# 2_isoSPI.net
KiCad netlist of a schematic drawn in Altium Designer
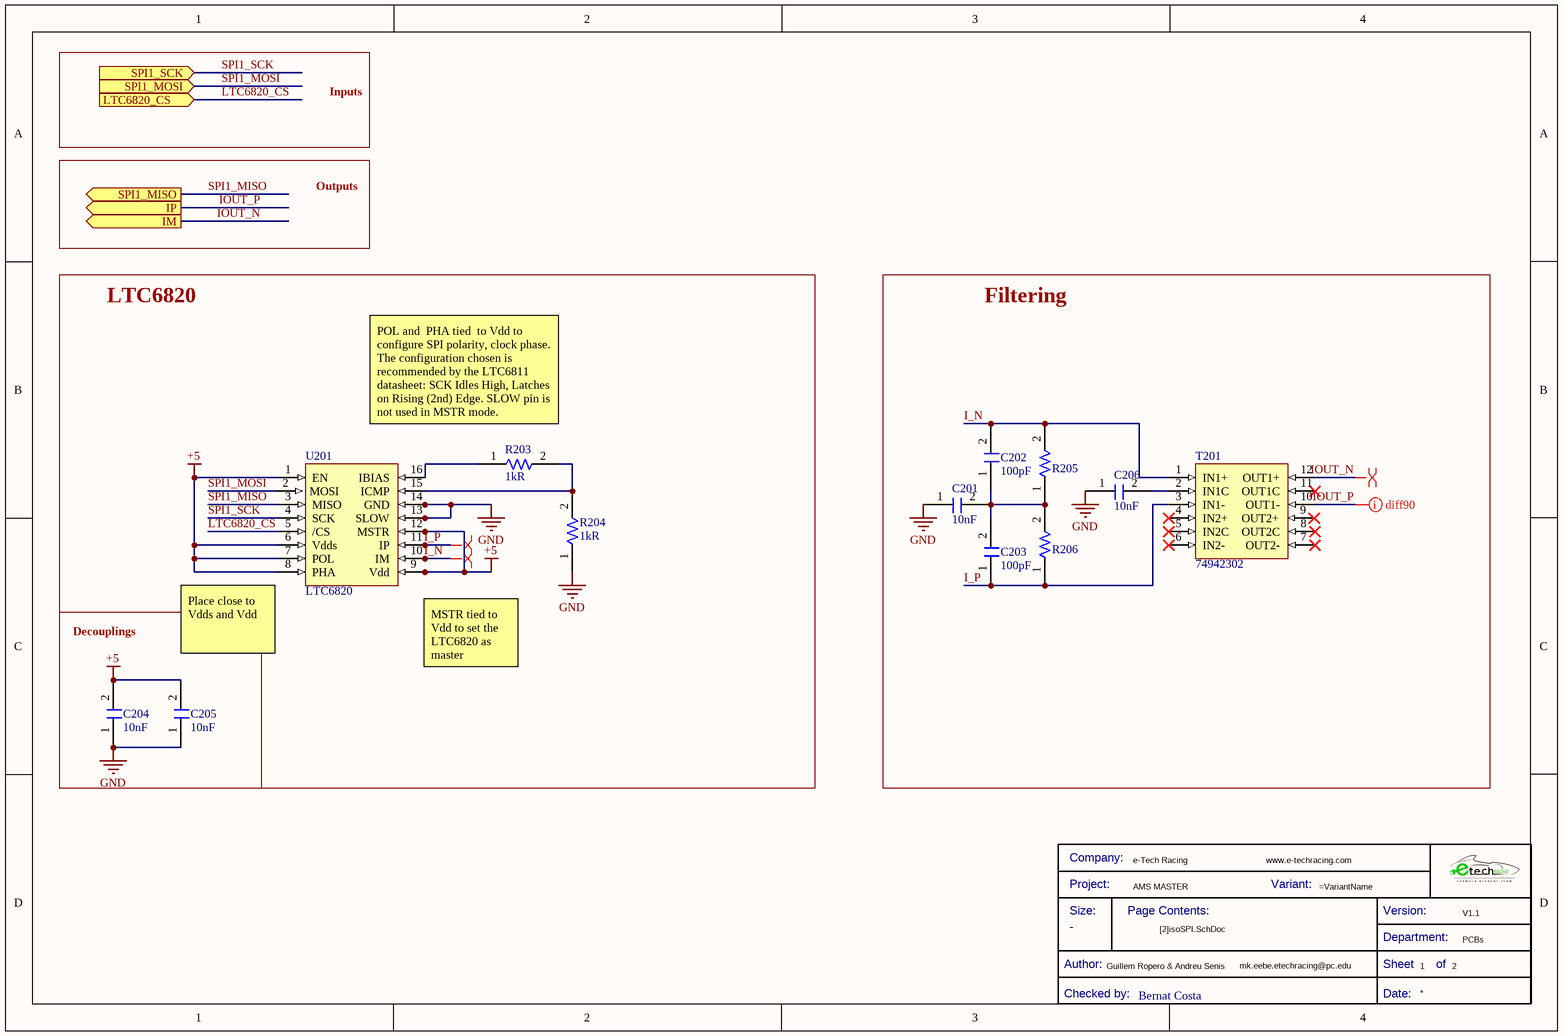
[diagram p0: [2]isoSPI.SchDoc]

(export (version "E")
  (design (tool "Eeschema 10.0.6"))
  (components
    (comp (ref "C201")
      (value "885012008055")
      (footprint "C1206FNPC-RW")
      (description "Cap Cer 10000PF 50V C0G/NP0 1206")
      (fields
        (field (name "MANUFACTURER") "Wurth Electronics")
        (field (name "TOLERANCE") "5%")
        (field (name "CAPACITANCE") "10nF")
        (field (name ".CREATOR") "DO")
      )
      (libsource (lib "Passives") (part "C10n-50V-1206FNPC-C0G/NP0"))
    )
    (comp (ref "C202")
      (value "885012007057")
      (footprint "C0805FNPC-W")
      (fields
        (field (name "MANUFACTURER") "Wurth Electronics")
        (field (name "TOLERANCE") "5%")
        (field (name "CAPACITANCE") "100pF")
        (field (name ".CREATOR") "DR")
      )
      (libsource (lib "Passives") (part "C100p-50V-0805FNPC-C0G/NP0"))
    )
    (comp (ref "C203")
      (value "885012007057")
      (footprint "C0805FNPC-W")
      (fields
        (field (name "MANUFACTURER") "Wurth Electronics")
        (field (name "TOLERANCE") "5%")
        (field (name "CAPACITANCE") "100pF")
        (field (name ".CREATOR") "DR")
      )
      (libsource (lib "Passives") (part "C100p-50V-0805FNPC-C0G/NP0"))
    )
    (comp (ref "C204")
      (value "885012207092")
      (footprint "C0805FNPC-R")
      (description "Cap, 0.01ΜF, 50V, 10%, X7R, 0805")
      (fields
        (field (name "TOLERANCE") "10%")
        (field (name "CAPACITANCE") "10nF")
        (field (name ".CREATOR") "DR")
      )
      (libsource (lib "Passives") (part "C10n-50V-0805FNPC-X7R"))
    )
    (comp (ref "C205")
      (value "885012207092")
      (footprint "C0805FNPC-R")
      (description "Cap, 0.01ΜF, 50V, 10%, X7R, 0805")
      (fields
        (field (name "TOLERANCE") "10%")
        (field (name "CAPACITANCE") "10nF")
        (field (name ".CREATOR") "DR")
      )
      (libsource (lib "Passives") (part "C10n-50V-0805FNPC-X7R"))
    )
    (comp (ref "C206")
      (value "885012008055")
      (footprint "C1206FNPC-RW")
      (description "Cap Cer 10000PF 50V C0G/NP0 1206")
      (fields
        (field (name "MANUFACTURER") "Wurth Electronics")
        (field (name "TOLERANCE") "5%")
        (field (name "CAPACITANCE") "10nF")
        (field (name ".CREATOR") "DO")
      )
      (libsource (lib "Passives") (part "C10n-50V-1206FNPC-C0G/NP0"))
    )
    (comp (ref "R203")
      (value "CR0805-JW-102ELF")
      (footprint "R0805FTK")
      (description "Res Thick Film 0805 1K Ohm 5% 1/8W ±200ppm/°C Molded SMD SMD Paper Tape on Plastic Reel")
      (fields
        (field (name "TOLERANCE") "5%")
        (field (name "RESISTANCE") "1kR")
        (field (name ".CREATOR") "GP")
      )
      (libsource (lib "Passives") (part "R1k-0805FTK"))
    )
    (comp (ref "R204")
      (value "CR0805-JW-102ELF")
      (footprint "R0805FTK")
      (description "Res Thick Film 0805 1K Ohm 5% 1/8W ±200ppm/°C Molded SMD SMD Paper Tape on Plastic Reel")
      (fields
        (field (name "TOLERANCE") "5%")
        (field (name "RESISTANCE") "1kR")
        (field (name ".CREATOR") "GP")
      )
      (libsource (lib "Passives") (part "R1k-0805FTK"))
    )
    (comp (ref "R205")
      (value "CRCW080550R0FKTA")
      (footprint "R0805FTK")
      (description "Res Thick Film 0805 50 Ohm 1% 0.125W(1/8W) ±100ppm/C Pad SMD Automotive T/R")
      (fields (field (name "MANUFACTURER") "Vishay Dale") (field (name "TOLERANCE") "1%"))
      (libsource (lib "Passives") (part "R50-0805FTK"))
    )
    (comp (ref "R206")
      (value "CRCW080550R0FKTA")
      (footprint "R0805FTK")
      (description "Res Thick Film 0805 50 Ohm 1% 0.125W(1/8W) ±100ppm/C Pad SMD Automotive T/R")
      (fields (field (name "MANUFACTURER") "Vishay Dale") (field (name "TOLERANCE") "1%"))
      (libsource (lib "Passives") (part "R50-0805FTK"))
    )
    (comp (ref "T201")
      (value "74942302")
      (footprint "TFMR_74942302")
      (libsource (lib "Filter components") (part "TFMR_4300V_1min_74942302"))
    )
    (comp (ref "U201")
      (value "LTC6820")
      (footprint "LTC6820")
      (description "IC COMM INTERFACE ISOSPI 16MSOP")
      (fields
        (field (name "MANUFACTURER") "Analog Devices / Linear Technology")
        (field (name "MANUFACTURER PART NUMBER") "LTC6820HMS#PBF")
      )
      (libsource (lib "Integrated circuits") (part "U_LTC6820"))
    )
  )
  (nets
    (net (code "1") (name "+5") (class "Default")
      (node (ref "C204") (pin "2") (pinfunction "2_2") (pintype "passive"))
      (node (ref "C205") (pin "2") (pinfunction "2_2") (pintype "passive"))
      (node (ref "U201") (pin "1") (pinfunction "EN_1") (pintype "input"))
      (node (ref "U201") (pin "12") (pinfunction "MSTR_12") (pintype "input"))
      (node (ref "U201") (pin "6") (pinfunction "Vdds_6") (pintype "input"))
      (node (ref "U201") (pin "7") (pinfunction "POL_7") (pintype "input"))
      (node (ref "U201") (pin "8") (pinfunction "PHA_8") (pintype "input"))
      (node (ref "U201") (pin "9") (pinfunction "Vdd_9") (pintype "input"))
    )
    (net (code "2") (name "/IOUT_N") (class "Default")
      (node (ref "T201") (pin "12") (pinfunction "OUT1+_12") (pintype "input"))
    )
    (net (code "3") (name "/IOUT_P") (class "Default")
      (node (ref "T201") (pin "10") (pinfunction "OUT1-_10") (pintype "input"))
    )
    (net (code "4") (name "/I_N") (class "Default")
      (node (ref "C202") (pin "2") (pinfunction "2_2") (pintype "passive"))
      (node (ref "R205") (pin "2") (pinfunction "2_2") (pintype "passive"))
      (node (ref "T201") (pin "1") (pinfunction "IN1+_1") (pintype "input"))
      (node (ref "U201") (pin "10") (pinfunction "IM_10") (pintype "input"))
    )
    (net (code "5") (name "/I_P") (class "Default")
      (node (ref "C203") (pin "1") (pinfunction "1_1") (pintype "passive"))
      (node (ref "R206") (pin "1") (pinfunction "1_1") (pintype "passive"))
      (node (ref "T201") (pin "3") (pinfunction "IN1-_3") (pintype "input"))
      (node (ref "U201") (pin "11") (pinfunction "IP_11") (pintype "input"))
    )
    (net (code "6") (name "/LTC6820_CS") (class "Default")
      (node (ref "U201") (pin "5") (pinfunction "/CS_5") (pintype "input"))
    )
    (net (code "7") (name "/SPI1_MISO") (class "Default")
      (node (ref "U201") (pin "3") (pinfunction "MISO_3") (pintype "input"))
    )
    (net (code "8") (name "/SPI1_MOSI") (class "Default")
      (node (ref "U201") (pin "2") (pinfunction "MOSI_2") (pintype "input"))
    )
    (net (code "9") (name "/SPI1_SCK") (class "Default")
      (node (ref "U201") (pin "4") (pinfunction "SCK_4") (pintype "input"))
    )
    (net (code "10") (name "GND") (class "Default")
      (node (ref "C201") (pin "1") (pinfunction "1_1") (pintype "passive"))
      (node (ref "C204") (pin "1") (pinfunction "1_1") (pintype "passive"))
      (node (ref "C205") (pin "1") (pinfunction "1_1") (pintype "passive"))
      (node (ref "C206") (pin "1") (pinfunction "1_1") (pintype "passive"))
      (node (ref "R204") (pin "1") (pinfunction "1_1") (pintype "passive"))
      (node (ref "U201") (pin "13") (pinfunction "SLOW_13") (pintype "input"))
      (node (ref "U201") (pin "14") (pinfunction "GND_14") (pintype "input"))
    )
    (net (code "11") (name "Net-(C201-Pad2)") (class "Default")
      (node (ref "C201") (pin "2") (pinfunction "2_2") (pintype "passive"))
      (node (ref "C202") (pin "1") (pinfunction "1_1") (pintype "passive"))
      (node (ref "C203") (pin "2") (pinfunction "2_2") (pintype "passive"))
      (node (ref "R205") (pin "1") (pinfunction "1_1") (pintype "passive"))
      (node (ref "R206") (pin "2") (pinfunction "2_2") (pintype "passive"))
    )
    (net (code "12") (name "Net-(T201-IN1C)") (class "Default")
      (node (ref "C206") (pin "2") (pinfunction "2_2") (pintype "passive"))
      (node (ref "T201") (pin "2") (pinfunction "IN1C_2") (pintype "input"))
    )
    (net (code "13") (name "Net-(U201-IBIAS)") (class "Default")
      (node (ref "R203") (pin "1") (pinfunction "1_1") (pintype "passive"))
      (node (ref "U201") (pin "16") (pinfunction "IBIAS_16") (pintype "input"))
    )
    (net (code "14") (name "Net-(U201-ICMP)") (class "Default")
      (node (ref "R203") (pin "2") (pinfunction "2_2") (pintype "passive"))
      (node (ref "R204") (pin "2") (pinfunction "2_2") (pintype "passive"))
      (node (ref "U201") (pin "15") (pinfunction "ICMP_15") (pintype "input"))
    )
    (net (code "15") (name "unconnected-(T201-IN2+-Pad4)") (class "Default")
      (node (ref "T201") (pin "4") (pinfunction "IN2+_4") (pintype "input+no_connect"))
    )
    (net (code "16") (name "unconnected-(T201-IN2--Pad6)") (class "Default")
      (node (ref "T201") (pin "6") (pinfunction "IN2-_6") (pintype "input+no_connect"))
    )
    (net (code "17") (name "unconnected-(T201-IN2C-Pad5)") (class "Default")
      (node (ref "T201") (pin "5") (pinfunction "IN2C_5") (pintype "input+no_connect"))
    )
    (net (code "18") (name "unconnected-(T201-OUT1C-Pad11)") (class "Default")
      (node (ref "T201") (pin "11") (pinfunction "OUT1C_11") (pintype "input+no_connect"))
    )
    (net (code "19") (name "unconnected-(T201-OUT2+-Pad9)") (class "Default")
      (node (ref "T201") (pin "9") (pinfunction "OUT2+_9") (pintype "input+no_connect"))
    )
    (net (code "20") (name "unconnected-(T201-OUT2--Pad7)") (class "Default")
      (node (ref "T201") (pin "7") (pinfunction "OUT2-_7") (pintype "input+no_connect"))
    )
    (net (code "21") (name "unconnected-(T201-OUT2C-Pad8)") (class "Default")
      (node (ref "T201") (pin "8") (pinfunction "OUT2C_8") (pintype "input+no_connect"))
    )
  )
)
